# Sending_end_2.net
KiCad netlist of a schematic drawn in EAGLE
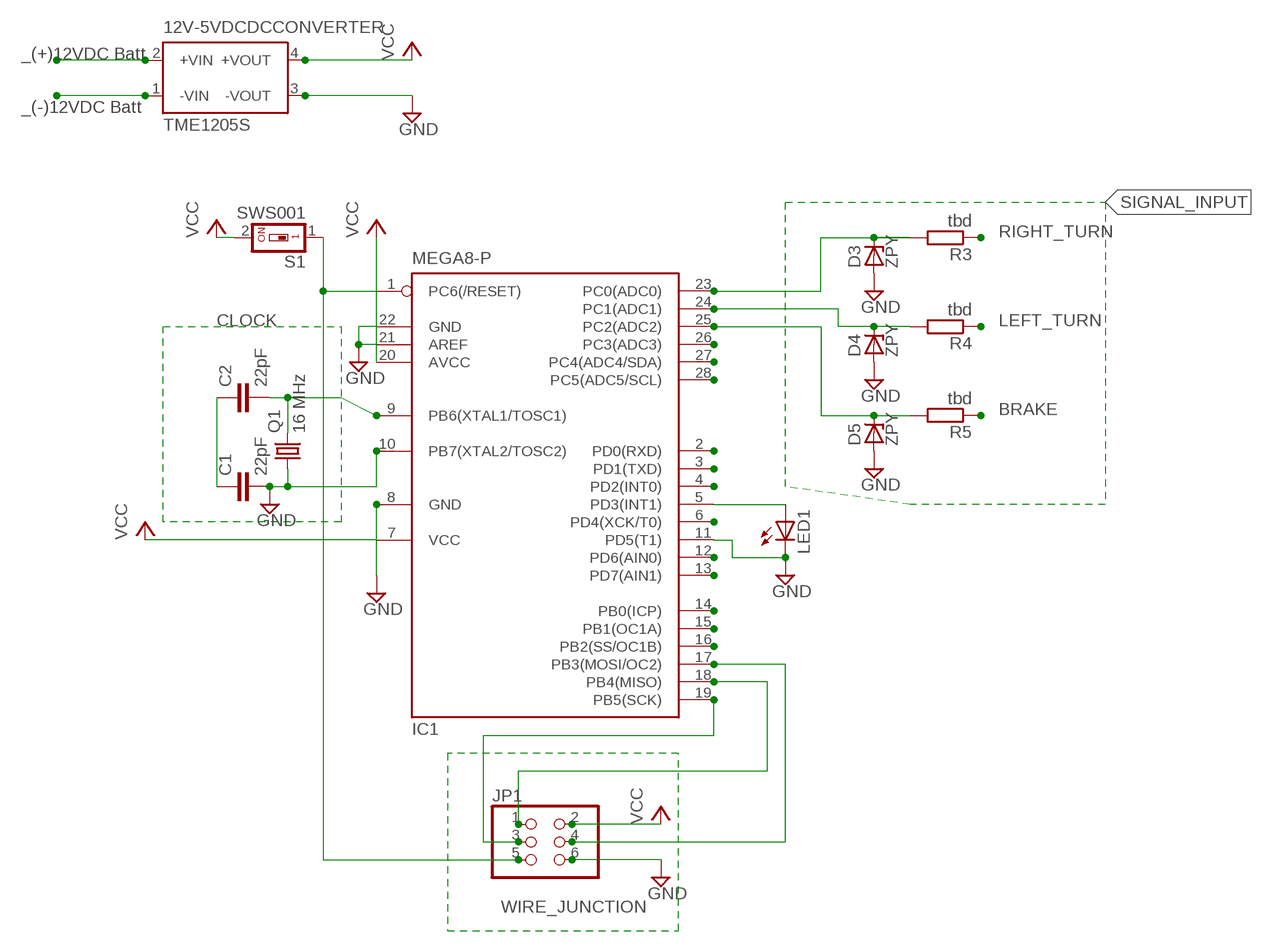
[diagram p0: schematic, sheet 1]

(export (version "E")
  (design (tool "Eeschema 10.0.6"))
  (components
    (comp (ref "12V-5VDCDCCONVERTER")
      (value "TME1205S")
      (footprint "eagle-import:TME")
      (fields
        (field (name "MPN") "TME 1205S")
        (field (name "MPN_1") "TME 1205S")
        (field (name "OC_FARNELL") "1007542")
        (field (name "OC_NEWARK") "51R5325")
      )
      (libsource (lib "eagle-import") (part "TME?1205S"))
    )
    (comp (ref "C1")
      (value "22pF")
      (footprint "eagle-import:C1210")
      (libsource (lib "eagle-import") (part "C-EUC1210"))
    )
    (comp (ref "C2")
      (value "22pF")
      (footprint "eagle-import:C1210")
      (libsource (lib "eagle-import") (part "C-EUC1210"))
    )
    (comp (ref "D3")
      (value "ZPY")
      (footprint "eagle-import:DO41Z10")
      (libsource (lib "eagle-import") (part "ZPY"))
    )
    (comp (ref "D4")
      (value "ZPY")
      (footprint "eagle-import:DO41Z10")
      (libsource (lib "eagle-import") (part "ZPY"))
    )
    (comp (ref "D5")
      (value "ZPY")
      (footprint "eagle-import:DO41Z10")
      (libsource (lib "eagle-import") (part "ZPY"))
    )
    (comp (ref "IC1")
      (value "MEGA8-P")
      (footprint "eagle-import:DIL28-3")
      (libsource (lib "eagle-import") (part "MEGA8-P"))
    )
    (comp (ref "JP1")
      (value "PINHD-2X3")
      (footprint "eagle-import:2X03")
      (libsource (lib "eagle-import") (part "PINHD-2X3"))
    )
    (comp (ref "LED1")
      (value "LEDCHIP-LED0603")
      (footprint "eagle-import:CHIP-LED0603")
      (libsource (lib "eagle-import") (part "LEDCHIP-LED0603"))
    )
    (comp (ref "Q1")
      (value "16 MHz")
      (footprint "eagle-import:HC49_S")
      (libsource (lib "eagle-import") (part "CRYSTALHC49S"))
    )
    (comp (ref "R3")
      (value "tbd")
      (footprint "eagle-import:M0805")
      (libsource (lib "eagle-import") (part "R-EU_M0805"))
    )
    (comp (ref "R4")
      (value "tbd")
      (footprint "eagle-import:M0805")
      (libsource (lib "eagle-import") (part "R-EU_M0805"))
    )
    (comp (ref "R5")
      (value "tbd")
      (footprint "eagle-import:M0805")
      (libsource (lib "eagle-import") (part "R-EU_M0805"))
    )
    (comp (ref "S1")
      (value "SWS001")
      (footprint "eagle-import:SMS-001")
      (libsource (lib "eagle-import") (part "SWS001"))
    )
  )
  (nets
    (net (code "1") (name "/BRAKE") (class "Default")
      (node (ref "R5") (pin "1") (pinfunction "1_1") (pintype "passive"))
    )
    (net (code "3") (name "/LEFT_TURN") (class "Default")
      (node (ref "R4") (pin "1") (pinfunction "1_1") (pintype "passive"))
    )
    (net (code "4") (name "/RIGHT_TURN") (class "Default")
      (node (ref "R3") (pin "1") (pinfunction "1_1") (pintype "passive"))
    )
    (net (code "6") (name "GND") (class "Default")
      (node (ref "12V-5VDCDCCONVERTER") (pin "3") (pinfunction "-VOUT_3") (pintype "passive"))
      (node (ref "C1") (pin "2") (pinfunction "2_2") (pintype "passive"))
      (node (ref "D3") (pin "A") (pinfunction "A_A") (pintype "passive"))
      (node (ref "D4") (pin "A") (pinfunction "A_A") (pintype "passive"))
      (node (ref "D5") (pin "A") (pinfunction "A_A") (pintype "passive"))
      (node (ref "IC1") (pin "10") (pinfunction "PB7(XTAL2/TOSC2)_10") (pintype "bidirectional"))
      (node (ref "IC1") (pin "11") (pinfunction "PD5(T1)_11") (pintype "bidirectional"))
      (node (ref "IC1") (pin "21") (pinfunction "AREF_21") (pintype "passive"))
      (node (ref "IC1") (pin "22") (pinfunction "GND_22") (pintype "power_in"))
      (node (ref "IC1") (pin "8") (pinfunction "GND_8") (pintype "power_in"))
      (node (ref "JP1") (pin "6") (pinfunction "6_6") (pintype "passive"))
      (node (ref "LED1") (pin "C") (pinfunction "C_C") (pintype "passive"))
      (node (ref "Q1") (pin "1") (pinfunction "1_1") (pintype "passive"))
    )
    (net (code "7") (name "Net-(C1-Pad1)") (class "Default")
      (node (ref "C1") (pin "1") (pinfunction "1_1") (pintype "passive"))
      (node (ref "C2") (pin "1") (pinfunction "1_1") (pintype "passive"))
    )
    (net (code "8") (name "Net-(IC1-PB3(MOSI{slash}OC2))") (class "Default")
      (node (ref "IC1") (pin "17") (pinfunction "PB3(MOSI/OC2)_17") (pintype "bidirectional"))
      (node (ref "JP1") (pin "4") (pinfunction "4_4") (pintype "passive"))
    )
    (net (code "9") (name "Net-(IC1-PB4(MISO))") (class "Default")
      (node (ref "IC1") (pin "18") (pinfunction "PB4(MISO)_18") (pintype "bidirectional"))
      (node (ref "JP1") (pin "1") (pinfunction "1_1") (pintype "passive"))
    )
    (net (code "10") (name "Net-(IC1-PB5(SCK))") (class "Default")
      (node (ref "IC1") (pin "19") (pinfunction "PB5(SCK)_19") (pintype "bidirectional"))
      (node (ref "JP1") (pin "3") (pinfunction "3_3") (pintype "passive"))
    )
    (net (code "11") (name "Net-(IC1-PB6(XTAL1{slash}TOSC1))") (class "Default")
      (node (ref "C2") (pin "2") (pinfunction "2_2") (pintype "passive"))
      (node (ref "IC1") (pin "9") (pinfunction "PB6(XTAL1/TOSC1)_9") (pintype "bidirectional"))
      (node (ref "Q1") (pin "2") (pinfunction "2_2") (pintype "passive"))
    )
    (net (code "12") (name "Net-(IC1-PC0(ADC0))") (class "Default")
      (node (ref "D3") (pin "C") (pinfunction "C_C") (pintype "passive"))
      (node (ref "IC1") (pin "23") (pinfunction "PC0(ADC0)_23") (pintype "bidirectional"))
      (node (ref "R3") (pin "2") (pinfunction "2_2") (pintype "passive"))
    )
    (net (code "13") (name "Net-(IC1-PC1(ADC1))") (class "Default")
      (node (ref "D4") (pin "C") (pinfunction "C_C") (pintype "passive"))
      (node (ref "IC1") (pin "24") (pinfunction "PC1(ADC1)_24") (pintype "bidirectional"))
      (node (ref "R4") (pin "2") (pinfunction "2_2") (pintype "passive"))
    )
    (net (code "14") (name "Net-(IC1-PC2(ADC2))") (class "Default")
      (node (ref "D5") (pin "C") (pinfunction "C_C") (pintype "passive"))
      (node (ref "IC1") (pin "25") (pinfunction "PC2(ADC2)_25") (pintype "bidirectional"))
      (node (ref "R5") (pin "2") (pinfunction "2_2") (pintype "passive"))
    )
    (net (code "15") (name "Net-(IC1-PC6({slash}RESET))") (class "Default")
      (node (ref "IC1") (pin "1") (pinfunction "PC6(/RESET)_1") (pintype "bidirectional"))
      (node (ref "JP1") (pin "5") (pinfunction "5_5") (pintype "passive"))
      (node (ref "S1") (pin "1") (pinfunction "1_1") (pintype "passive"))
    )
    (net (code "16") (name "Net-(IC1-PD3(INT1))") (class "Default")
      (node (ref "IC1") (pin "5") (pinfunction "PD3(INT1)_5") (pintype "bidirectional"))
      (node (ref "LED1") (pin "A") (pinfunction "A_A") (pintype "passive"))
    )
    (net (code "18") (name "VCC") (class "Default")
      (node (ref "12V-5VDCDCCONVERTER") (pin "4") (pinfunction "+VOUT_4") (pintype "passive"))
      (node (ref "IC1") (pin "20") (pinfunction "AVCC_20") (pintype "power_in"))
      (node (ref "IC1") (pin "7") (pinfunction "VCC_7") (pintype "power_in"))
      (node (ref "JP1") (pin "2") (pinfunction "2_2") (pintype "passive"))
      (node (ref "S1") (pin "2") (pinfunction "2_2") (pintype "passive"))
    )
    (net (code "19") (name "unconnected-(12V-5VDCDCCONVERTER-+VIN-Pad2)") (class "Default")
      (node (ref "12V-5VDCDCCONVERTER") (pin "2") (pinfunction "+VIN_2") (pintype "passive"))
    )
    (net (code "20") (name "unconnected-(12V-5VDCDCCONVERTER--VIN-Pad1)") (class "Default")
      (node (ref "12V-5VDCDCCONVERTER") (pin "1") (pinfunction "-VIN_1") (pintype "passive"))
    )
    (net (code "21") (name "unconnected-(IC1-PB0(ICP)-Pad14)") (class "Default")
      (node (ref "IC1") (pin "14") (pinfunction "PB0(ICP)_14") (pintype "bidirectional"))
    )
    (net (code "22") (name "unconnected-(IC1-PB1(OC1A)-Pad15)") (class "Default")
      (node (ref "IC1") (pin "15") (pinfunction "PB1(OC1A)_15") (pintype "bidirectional"))
    )
    (net (code "23") (name "unconnected-(IC1-PB2(SS{slash}OC1B)-Pad16)") (class "Default")
      (node (ref "IC1") (pin "16") (pinfunction "PB2(SS/OC1B)_16") (pintype "bidirectional"))
    )
    (net (code "24") (name "unconnected-(IC1-PC3(ADC3)-Pad26)") (class "Default")
      (node (ref "IC1") (pin "26") (pinfunction "PC3(ADC3)_26") (pintype "bidirectional"))
    )
    (net (code "25") (name "unconnected-(IC1-PC4(ADC4{slash}SDA)-Pad27)") (class "Default")
      (node (ref "IC1") (pin "27") (pinfunction "PC4(ADC4/SDA)_27") (pintype "bidirectional"))
    )
    (net (code "26") (name "unconnected-(IC1-PC5(ADC5{slash}SCL)-Pad28)") (class "Default")
      (node (ref "IC1") (pin "28") (pinfunction "PC5(ADC5/SCL)_28") (pintype "bidirectional"))
    )
    (net (code "27") (name "unconnected-(IC1-PD0(RXD)-Pad2)") (class "Default")
      (node (ref "IC1") (pin "2") (pinfunction "PD0(RXD)_2") (pintype "bidirectional"))
    )
    (net (code "28") (name "unconnected-(IC1-PD1(TXD)-Pad3)") (class "Default")
      (node (ref "IC1") (pin "3") (pinfunction "PD1(TXD)_3") (pintype "bidirectional"))
    )
    (net (code "29") (name "unconnected-(IC1-PD2(INT0)-Pad4)") (class "Default")
      (node (ref "IC1") (pin "4") (pinfunction "PD2(INT0)_4") (pintype "bidirectional"))
    )
    (net (code "30") (name "unconnected-(IC1-PD4(XCK{slash}T0)-Pad6)") (class "Default")
      (node (ref "IC1") (pin "6") (pinfunction "PD4(XCK/T0)_6") (pintype "bidirectional"))
    )
    (net (code "31") (name "unconnected-(IC1-PD6(AIN0)-Pad12)") (class "Default")
      (node (ref "IC1") (pin "12") (pinfunction "PD6(AIN0)_12") (pintype "bidirectional"))
    )
    (net (code "32") (name "unconnected-(IC1-PD7(AIN1)-Pad13)") (class "Default")
      (node (ref "IC1") (pin "13") (pinfunction "PD7(AIN1)_13") (pintype "bidirectional"))
    )
  )
)
